# sensorMesh_nano.net
KiCad netlist of a schematic drawn in Altium Designer
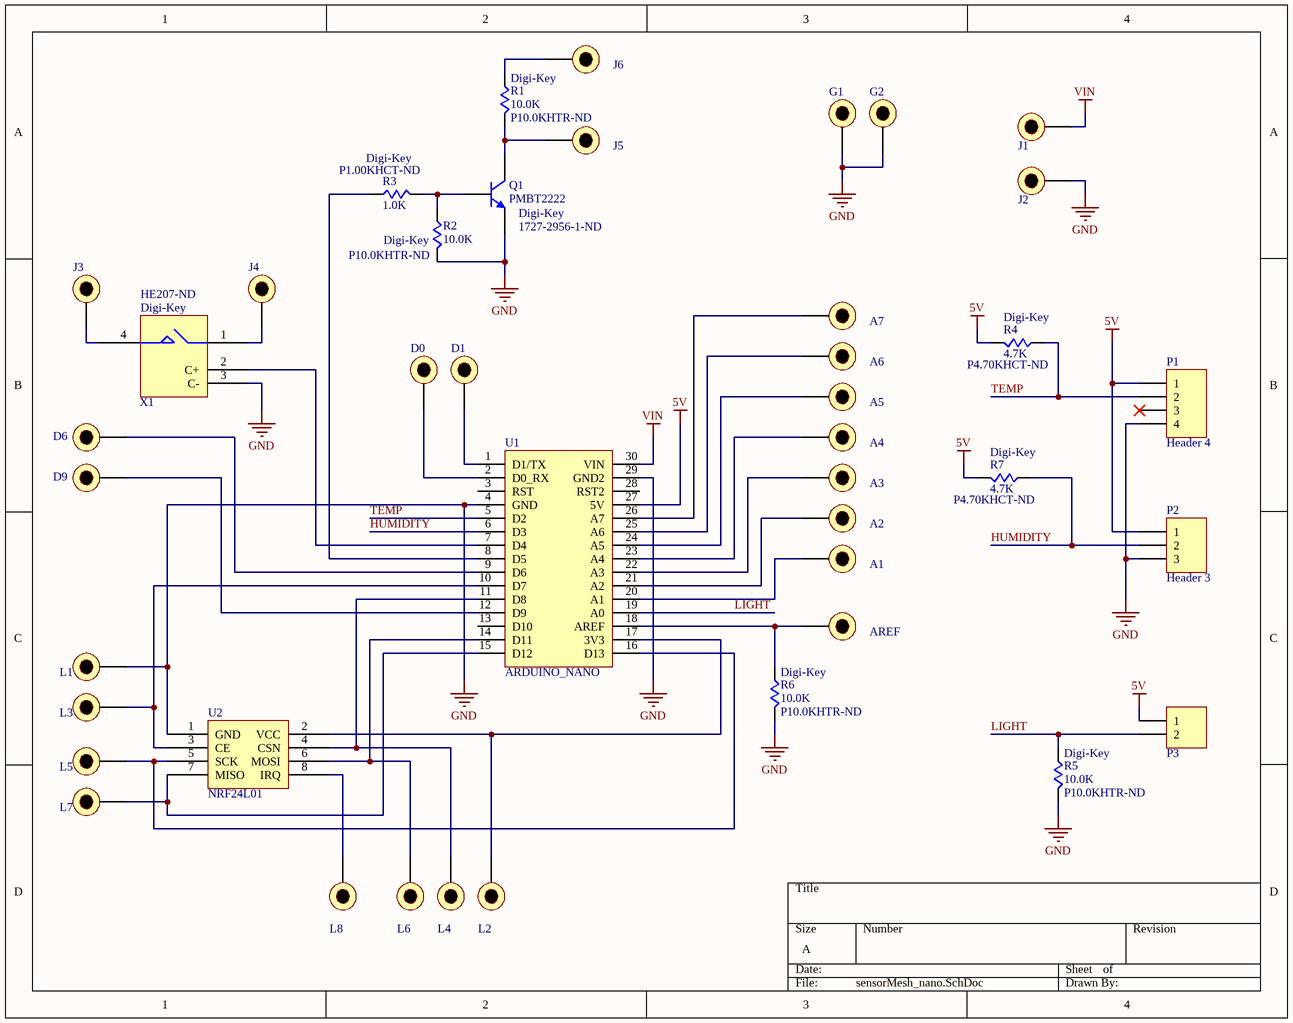
[diagram p0: sensorMesh_nano.SchDoc]

(export (version "E")
  (design (tool "Eeschema 10.0.6"))
  (components
    (comp (ref "A1")
      (value "WIRE_HOLE")
      (footprint "20awg-wire")
      (libsource (lib "MAST_Library") (part "WIRE_HOLE"))
    )
    (comp (ref "A2")
      (value "WIRE_HOLE")
      (footprint "20awg-wire")
      (libsource (lib "MAST_Library") (part "WIRE_HOLE"))
    )
    (comp (ref "A3")
      (value "WIRE_HOLE")
      (footprint "20awg-wire")
      (libsource (lib "MAST_Library") (part "WIRE_HOLE"))
    )
    (comp (ref "A4")
      (value "WIRE_HOLE")
      (footprint "20awg-wire")
      (libsource (lib "MAST_Library") (part "WIRE_HOLE"))
    )
    (comp (ref "A5")
      (value "WIRE_HOLE")
      (footprint "20awg-wire")
      (libsource (lib "MAST_Library") (part "WIRE_HOLE"))
    )
    (comp (ref "A6")
      (value "WIRE_HOLE")
      (footprint "20awg-wire")
      (libsource (lib "MAST_Library") (part "WIRE_HOLE"))
    )
    (comp (ref "A7")
      (value "WIRE_HOLE")
      (footprint "20awg-wire")
      (libsource (lib "MAST_Library") (part "WIRE_HOLE"))
    )
    (comp (ref "AREF")
      (value "WIRE_HOLE")
      (footprint "20awg-wire")
      (libsource (lib "MAST_Library") (part "WIRE_HOLE"))
    )
    (comp (ref "D0")
      (value "WIRE_HOLE")
      (footprint "20awg-wire")
      (libsource (lib "MAST_Library") (part "WIRE_HOLE"))
    )
    (comp (ref "D1")
      (value "WIRE_HOLE")
      (footprint "20awg-wire")
      (libsource (lib "MAST_Library") (part "WIRE_HOLE"))
    )
    (comp (ref "D6")
      (value "WIRE_HOLE")
      (footprint "20awg-wire")
      (libsource (lib "MAST_Library") (part "WIRE_HOLE"))
    )
    (comp (ref "D9")
      (value "WIRE_HOLE")
      (footprint "20awg-wire")
      (libsource (lib "MAST_Library") (part "WIRE_HOLE"))
    )
    (comp (ref "G1")
      (value "WIRE_HOLE")
      (footprint "20awg-wire")
      (libsource (lib "MAST_Library") (part "WIRE_HOLE"))
    )
    (comp (ref "G2")
      (value "WIRE_HOLE")
      (footprint "20awg-wire")
      (libsource (lib "MAST_Library") (part "WIRE_HOLE"))
    )
    (comp (ref "J1")
      (value "WIRE_HOLE")
      (footprint "18awg-wire")
      (libsource (lib "MAST_Library") (part "WIRE_HOLE"))
    )
    (comp (ref "J2")
      (value "WIRE_HOLE")
      (footprint "18awg-wire")
      (libsource (lib "MAST_Library") (part "WIRE_HOLE"))
    )
    (comp (ref "J3")
      (value "WIRE_HOLE")
      (footprint "20awg-wire")
      (libsource (lib "MAST_Library") (part "WIRE_HOLE"))
    )
    (comp (ref "J4")
      (value "WIRE_HOLE")
      (footprint "20awg-wire")
      (libsource (lib "MAST_Library") (part "WIRE_HOLE"))
    )
    (comp (ref "J5")
      (value "WIRE_HOLE")
      (footprint "20awg-wire")
      (libsource (lib "MAST_Library") (part "WIRE_HOLE"))
    )
    (comp (ref "J6")
      (value "WIRE_HOLE")
      (footprint "20awg-wire")
      (libsource (lib "MAST_Library") (part "WIRE_HOLE"))
    )
    (comp (ref "L1")
      (value "WIRE_HOLE")
      (footprint "24awg-wire - ROUND")
      (libsource (lib "HCG_Library") (part "WIRE_HOLE"))
    )
    (comp (ref "L2")
      (value "WIRE_HOLE")
      (footprint "24awg-wire - ROUND")
      (libsource (lib "HCG_Library") (part "WIRE_HOLE"))
    )
    (comp (ref "L3")
      (value "WIRE_HOLE")
      (footprint "24awg-wire - ROUND")
      (libsource (lib "HCG_Library") (part "WIRE_HOLE"))
    )
    (comp (ref "L4")
      (value "WIRE_HOLE")
      (footprint "24awg-wire - ROUND")
      (libsource (lib "HCG_Library") (part "WIRE_HOLE"))
    )
    (comp (ref "L5")
      (value "WIRE_HOLE")
      (footprint "24awg-wire - ROUND")
      (libsource (lib "HCG_Library") (part "WIRE_HOLE"))
    )
    (comp (ref "L6")
      (value "WIRE_HOLE")
      (footprint "24awg-wire - ROUND")
      (libsource (lib "HCG_Library") (part "WIRE_HOLE"))
    )
    (comp (ref "L7")
      (value "WIRE_HOLE")
      (footprint "24awg-wire - ROUND")
      (libsource (lib "HCG_Library") (part "WIRE_HOLE"))
    )
    (comp (ref "L8")
      (value "WIRE_HOLE")
      (footprint "24awg-wire - ROUND")
      (libsource (lib "HCG_Library") (part "WIRE_HOLE"))
    )
    (comp (ref "P1")
      (value "Header 4")
      (footprint "HDR1X4")
      (description "Header, 4-Pin")
      (fields (field (name "PUBLISHER") "Altium Limited"))
      (libsource (lib "Miscellaneous Connectors") (part "Header 4"))
    )
    (comp (ref "P2")
      (value "Header 3")
      (footprint "HDR1X3")
      (description "Header, 3-Pin")
      (fields (field (name "PUBLISHER") "Altium Limited"))
      (libsource (lib "Miscellaneous Connectors") (part "Header 3"))
    )
    (comp (ref "P3")
      (value "Header 2")
      (footprint "HDR1X2")
      (description "CONN HEADER 2POS .100\" STR GOLD")
      (libsource (lib "MAST_Library") (part "Header 2"))
    )
    (comp (ref "Q1")
      (value "PMBT2222")
      (footprint "SOT23_N")
      (description "NPN Switching Transistor")
      (fields (field (name "SUPPLIER 1") "Digi-Key") (field (name "SUPPLIER PART NUMBER 1") "1727-2956-1-ND"))
      (libsource (lib "MAST_Library") (part "NPN"))
    )
    (comp (ref "R1")
      (value "10.0K")
      (footprint "RESC1005N")
      (description "Resistor")
      (fields
        (field (name "SUPPLIER 1") "Digi-Key")
        (field (name "SUPPLIER PART NUMBER 1") "P10.0KHTR-ND")
        (field (name "Comment") "R")
      )
      (libsource (lib "HCG_COMPONENTS") (part "R"))
    )
    (comp (ref "R2")
      (value "10.0K")
      (footprint "RESC1005N")
      (description "Resistor")
      (fields
        (field (name "SUPPLIER 1") "Digi-Key")
        (field (name "SUPPLIER PART NUMBER 1") "P10.0KHTR-ND")
        (field (name "Comment") "R")
      )
      (libsource (lib "HCG_COMPONENTS") (part "R"))
    )
    (comp (ref "R3")
      (value "1.0K")
      (footprint "RESC1005N")
      (description "Resistor")
      (fields
        (field (name "SUPPLIER 1") "Digi-Key")
        (field (name "SUPPLIER PART NUMBER 1") "P1.00KHCT-ND")
        (field (name "Comment") "R")
      )
      (libsource (lib "HCG_COMPONENTS") (part "R"))
    )
    (comp (ref "R4")
      (value "4.7K")
      (footprint "RESC1005N")
      (description "Resistor")
      (fields
        (field (name "SUPPLIER 1") "Digi-Key")
        (field (name "SUPPLIER PART NUMBER 1") "P4.70KHCT-ND")
        (field (name "Comment") "R")
      )
      (libsource (lib "HCG_COMPONENTS") (part "R"))
    )
    (comp (ref "R5")
      (value "10.0K")
      (footprint "RESC1005N")
      (description "Resistor")
      (fields
        (field (name "SUPPLIER 1") "Digi-Key")
        (field (name "SUPPLIER PART NUMBER 1") "P10.0KHTR-ND")
        (field (name "Comment") "R")
      )
      (libsource (lib "HCG_COMPONENTS") (part "R"))
    )
    (comp (ref "R6")
      (value "10.0K")
      (footprint "RESC1005N")
      (description "Resistor")
      (fields
        (field (name "SUPPLIER 1") "Digi-Key")
        (field (name "SUPPLIER PART NUMBER 1") "P10.0KHTR-ND")
        (field (name "Comment") "R")
      )
      (libsource (lib "HCG_COMPONENTS") (part "R"))
    )
    (comp (ref "R7")
      (value "4.7K")
      (footprint "RESC1005N")
      (description "Resistor")
      (fields
        (field (name "SUPPLIER 1") "Digi-Key")
        (field (name "SUPPLIER PART NUMBER 1") "P4.70KHCT-ND")
        (field (name "Comment") "R")
      )
      (libsource (lib "HCG_COMPONENTS") (part "R"))
    )
    (comp (ref "U1")
      (value "ARDUINO_NANO")
      (footprint "ARDUINO_NANO")
      (description "ARDUINO NANO MODULE")
      (libsource (lib "HCG_Library") (part "Arduino_Nano"))
    )
    (comp (ref "U2")
      (value "NRF24L01")
      (footprint "NRF24L01")
      (libsource (lib "HCG_Library") (part "NRF24L01"))
    )
    (comp (ref "X1")
      (value "REED_RELAY")
      (footprint "HE3600")
      (fields (field (name "SUPPLIER 1") "Digi-Key") (field (name "SUPPLIER PART NUMBER 1") "HE207-ND"))
      (libsource (lib "HCG_Library") (part "REED_RELAY"))
    )
  )
  (nets
    (net (code "1") (name "/HUMIDITY") (class "Default")
      (node (ref "P2") (pin "2") (pinfunction "2_2") (pintype "passive"))
      (node (ref "R7") (pin "1") (pinfunction "1_1") (pintype "passive"))
      (node (ref "U1") (pin "6") (pinfunction "D3_6") (pintype "passive"))
    )
    (net (code "2") (name "/LIGHT") (class "Default")
      (node (ref "P3") (pin "2") (pinfunction "2_2") (pintype "passive"))
      (node (ref "R5") (pin "1") (pinfunction "1_1") (pintype "passive"))
      (node (ref "U1") (pin "19") (pinfunction "A0_19") (pintype "passive"))
    )
    (net (code "3") (name "/TEMP") (class "Default")
      (node (ref "P1") (pin "2") (pinfunction "2_2") (pintype "passive"))
      (node (ref "R4") (pin "1") (pinfunction "1_1") (pintype "passive"))
      (node (ref "U1") (pin "5") (pinfunction "D2_5") (pintype "passive"))
    )
    (net (code "4") (name "5V") (class "Default")
      (node (ref "P1") (pin "1") (pinfunction "1_1") (pintype "passive"))
      (node (ref "P2") (pin "1") (pinfunction "1_1") (pintype "passive"))
      (node (ref "P3") (pin "1") (pinfunction "1_1") (pintype "passive"))
      (node (ref "R4") (pin "2") (pinfunction "2_2") (pintype "passive"))
      (node (ref "R7") (pin "2") (pinfunction "2_2") (pintype "passive"))
      (node (ref "U1") (pin "27") (pinfunction "5V_27") (pintype "passive"))
    )
    (net (code "5") (name "GND") (class "Default")
      (node (ref "G1") (pin "1") (pinfunction "1_1") (pintype "passive"))
      (node (ref "G2") (pin "1") (pinfunction "1_1") (pintype "passive"))
      (node (ref "J2") (pin "1") (pinfunction "1_1") (pintype "passive"))
      (node (ref "L1") (pin "1") (pinfunction "1_1") (pintype "passive"))
      (node (ref "P1") (pin "4") (pinfunction "4_4") (pintype "passive"))
      (node (ref "P2") (pin "3") (pinfunction "3_3") (pintype "passive"))
      (node (ref "Q1") (pin "2") (pinfunction "E_2") (pintype "passive"))
      (node (ref "R2") (pin "2") (pinfunction "2_2") (pintype "passive"))
      (node (ref "R5") (pin "2") (pinfunction "2_2") (pintype "passive"))
      (node (ref "R6") (pin "2") (pinfunction "2_2") (pintype "passive"))
      (node (ref "U1") (pin "29") (pinfunction "GND2_29") (pintype "passive"))
      (node (ref "U1") (pin "4") (pinfunction "GND_4") (pintype "passive"))
      (node (ref "U2") (pin "1") (pinfunction "GND_1") (pintype "passive"))
      (node (ref "X1") (pin "3") (pinfunction "C-_3") (pintype "passive"))
    )
    (net (code "6") (name "Net-(J6-Pad1)") (class "Default")
      (node (ref "J6") (pin "1") (pinfunction "1_1") (pintype "passive"))
      (node (ref "R1") (pin "1") (pinfunction "1_1") (pintype "passive"))
    )
    (net (code "7") (name "Net-(Q1-B)") (class "Default")
      (node (ref "Q1") (pin "1") (pinfunction "B_1") (pintype "passive"))
      (node (ref "R2") (pin "1") (pinfunction "1_1") (pintype "passive"))
      (node (ref "R3") (pin "2") (pinfunction "2_2") (pintype "passive"))
    )
    (net (code "8") (name "Net-(Q1-C)") (class "Default")
      (node (ref "J5") (pin "1") (pinfunction "1_1") (pintype "passive"))
      (node (ref "Q1") (pin "3") (pinfunction "C_3") (pintype "passive"))
      (node (ref "R1") (pin "2") (pinfunction "2_2") (pintype "passive"))
    )
    (net (code "9") (name "Net-(U1-3V3)") (class "Default")
      (node (ref "L2") (pin "1") (pinfunction "1_1") (pintype "passive"))
      (node (ref "U1") (pin "17") (pinfunction "3V3_17") (pintype "passive"))
      (node (ref "U2") (pin "2") (pinfunction "VCC_2") (pintype "passive"))
    )
    (net (code "10") (name "Net-(U1-A1)") (class "Default")
      (node (ref "A1") (pin "1") (pinfunction "1_1") (pintype "passive"))
      (node (ref "U1") (pin "20") (pinfunction "A1_20") (pintype "passive"))
    )
    (net (code "11") (name "Net-(U1-A2)") (class "Default")
      (node (ref "A2") (pin "1") (pinfunction "1_1") (pintype "passive"))
      (node (ref "U1") (pin "21") (pinfunction "A2_21") (pintype "passive"))
    )
    (net (code "12") (name "Net-(U1-A3)") (class "Default")
      (node (ref "A3") (pin "1") (pinfunction "1_1") (pintype "passive"))
      (node (ref "U1") (pin "22") (pinfunction "A3_22") (pintype "passive"))
    )
    (net (code "13") (name "Net-(U1-A4)") (class "Default")
      (node (ref "A4") (pin "1") (pinfunction "1_1") (pintype "passive"))
      (node (ref "U1") (pin "23") (pinfunction "A4_23") (pintype "passive"))
    )
    (net (code "14") (name "Net-(U1-A5)") (class "Default")
      (node (ref "A5") (pin "1") (pinfunction "1_1") (pintype "passive"))
      (node (ref "U1") (pin "24") (pinfunction "A5_24") (pintype "passive"))
    )
    (net (code "15") (name "Net-(U1-A6)") (class "Default")
      (node (ref "A6") (pin "1") (pinfunction "1_1") (pintype "passive"))
      (node (ref "U1") (pin "25") (pinfunction "A6_25") (pintype "passive"))
    )
    (net (code "16") (name "Net-(U1-A7)") (class "Default")
      (node (ref "A7") (pin "1") (pinfunction "1_1") (pintype "passive"))
      (node (ref "U1") (pin "26") (pinfunction "A7_26") (pintype "passive"))
    )
    (net (code "17") (name "Net-(U1-AREF)") (class "Default")
      (node (ref "AREF") (pin "1") (pinfunction "1_1") (pintype "passive"))
      (node (ref "R6") (pin "1") (pinfunction "1_1") (pintype "passive"))
      (node (ref "U1") (pin "18") (pinfunction "AREF_18") (pintype "passive"))
    )
    (net (code "18") (name "Net-(U1-D0_RX)") (class "Default")
      (node (ref "D0") (pin "1") (pinfunction "1_1") (pintype "passive"))
      (node (ref "U1") (pin "2") (pinfunction "D0_RX_2") (pintype "passive"))
    )
    (net (code "19") (name "Net-(U1-D1{slash}TX)") (class "Default")
      (node (ref "D1") (pin "1") (pinfunction "1_1") (pintype "passive"))
      (node (ref "U1") (pin "1") (pinfunction "D1/TX_1") (pintype "passive"))
    )
    (net (code "20") (name "Net-(U1-D4)") (class "Default")
      (node (ref "U1") (pin "7") (pinfunction "D4_7") (pintype "passive"))
      (node (ref "X1") (pin "2") (pinfunction "C+_2") (pintype "passive"))
    )
    (net (code "21") (name "Net-(U1-D5)") (class "Default")
      (node (ref "R3") (pin "1") (pinfunction "1_1") (pintype "passive"))
      (node (ref "U1") (pin "8") (pinfunction "D5_8") (pintype "passive"))
    )
    (net (code "22") (name "Net-(U1-D6)") (class "Default")
      (node (ref "D6") (pin "1") (pinfunction "1_1") (pintype "passive"))
      (node (ref "U1") (pin "9") (pinfunction "D6_9") (pintype "passive"))
    )
    (net (code "23") (name "Net-(U1-D7)") (class "Default")
      (node (ref "L3") (pin "1") (pinfunction "1_1") (pintype "passive"))
      (node (ref "U1") (pin "10") (pinfunction "D7_10") (pintype "passive"))
      (node (ref "U2") (pin "3") (pinfunction "CE_3") (pintype "passive"))
    )
    (net (code "24") (name "Net-(U1-D8)") (class "Default")
      (node (ref "L4") (pin "1") (pinfunction "1_1") (pintype "passive"))
      (node (ref "U1") (pin "11") (pinfunction "D8_11") (pintype "passive"))
      (node (ref "U2") (pin "4") (pinfunction "CSN_4") (pintype "passive"))
    )
    (net (code "25") (name "Net-(U1-D9)") (class "Default")
      (node (ref "D9") (pin "1") (pinfunction "1_1") (pintype "passive"))
      (node (ref "U1") (pin "12") (pinfunction "D9_12") (pintype "passive"))
    )
    (net (code "26") (name "Net-(U1-D11)") (class "Default")
      (node (ref "L6") (pin "1") (pinfunction "1_1") (pintype "passive"))
      (node (ref "U1") (pin "14") (pinfunction "D11_14") (pintype "passive"))
      (node (ref "U2") (pin "6") (pinfunction "MOSI_6") (pintype "passive"))
    )
    (net (code "27") (name "Net-(U1-D12)") (class "Default")
      (node (ref "L7") (pin "1") (pinfunction "1_1") (pintype "passive"))
      (node (ref "U1") (pin "15") (pinfunction "D12_15") (pintype "passive"))
      (node (ref "U2") (pin "7") (pinfunction "MISO_7") (pintype "passive"))
    )
    (net (code "28") (name "Net-(U1-D13)") (class "Default")
      (node (ref "L5") (pin "1") (pinfunction "1_1") (pintype "passive"))
      (node (ref "U1") (pin "16") (pinfunction "D13_16") (pintype "passive"))
      (node (ref "U2") (pin "5") (pinfunction "SCK_5") (pintype "passive"))
    )
    (net (code "29") (name "Net-(U2-IRQ)") (class "Default")
      (node (ref "L8") (pin "1") (pinfunction "1_1") (pintype "passive"))
      (node (ref "U2") (pin "8") (pinfunction "IRQ_8") (pintype "passive"))
    )
    (net (code "30") (name "Net-(X1-SW1)") (class "Default")
      (node (ref "J4") (pin "1") (pinfunction "1_1") (pintype "passive"))
      (node (ref "X1") (pin "1") (pinfunction "SW1_1") (pintype "passive"))
    )
    (net (code "31") (name "Net-(X1-SW2)") (class "Default")
      (node (ref "J3") (pin "1") (pinfunction "1_1") (pintype "passive"))
      (node (ref "X1") (pin "4") (pinfunction "SW2_4") (pintype "passive"))
    )
    (net (code "32") (name "VIN") (class "Default")
      (node (ref "J1") (pin "1") (pinfunction "1_1") (pintype "passive"))
      (node (ref "U1") (pin "30") (pinfunction "VIN_30") (pintype "passive"))
    )
    (net (code "33") (name "unconnected-(P1-Pad3)") (class "Default")
      (node (ref "P1") (pin "3") (pinfunction "3_3") (pintype "passive+no_connect"))
    )
    (net (code "34") (name "unconnected-(U1-D10-Pad13)") (class "Default")
      (node (ref "U1") (pin "13") (pinfunction "D10_13") (pintype "passive"))
    )
    (net (code "35") (name "unconnected-(U1-RST-Pad3)") (class "Default")
      (node (ref "U1") (pin "3") (pinfunction "RST_3") (pintype "passive"))
    )
    (net (code "36") (name "unconnected-(U1-RST2-Pad28)") (class "Default")
      (node (ref "U1") (pin "28") (pinfunction "RST2_28") (pintype "passive"))
    )
  )
)
